# ELEC327_V4.net
KiCad netlist of a schematic drawn in EAGLE
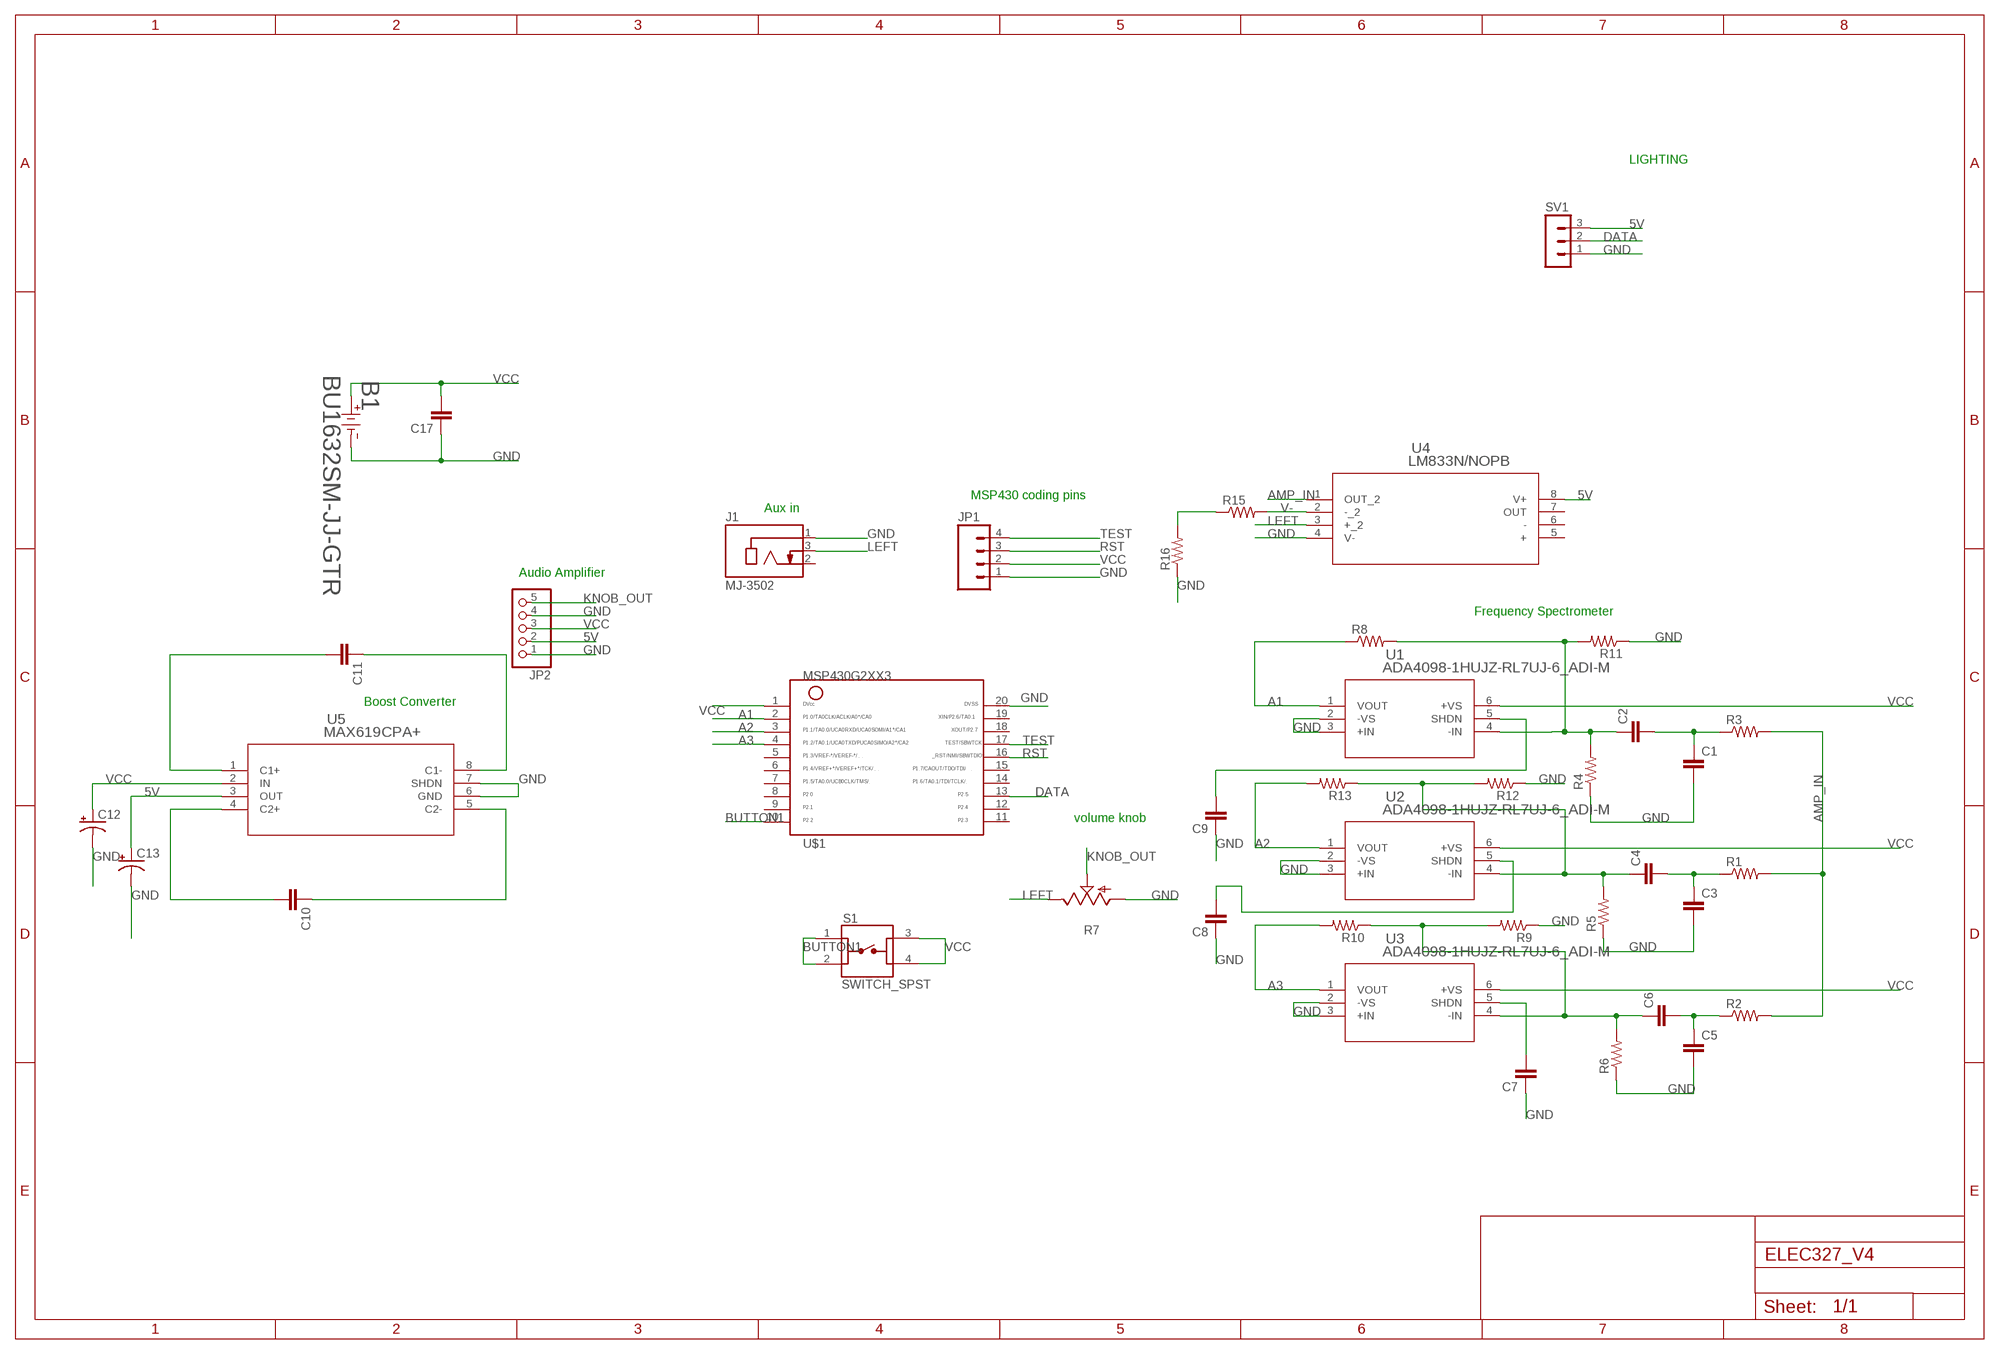
[diagram p0: schematic, sheet 1]

(export (version "E")
  (design (tool "Eeschema 10.0.6"))
  (components
    (comp (ref "B1")
      (value "BU1632SM-JJ-GTR")
      (footprint "eagle-import:BU1632SM-JJ-GTR_MPD")
      (fields (field (name "COPYRIGHT") "Copyright (C) 2023 Ultra Librarian. All rights reserved."))
      (libsource (lib "eagle-import") (part "BU1632SM-JJ-GTR"))
    )
    (comp (ref "C1")
      (value "C-EUC1206")
      (footprint "eagle-import:C1206")
      (libsource (lib "eagle-import") (part "C-EUC1206"))
    )
    (comp (ref "C2")
      (value "C-EUC1206")
      (footprint "eagle-import:C1206")
      (libsource (lib "eagle-import") (part "C-EUC1206"))
    )
    (comp (ref "C3")
      (value "C-EUC1206")
      (footprint "eagle-import:C1206")
      (libsource (lib "eagle-import") (part "C-EUC1206"))
    )
    (comp (ref "C4")
      (value "C-EUC1206")
      (footprint "eagle-import:C1206")
      (libsource (lib "eagle-import") (part "C-EUC1206"))
    )
    (comp (ref "C5")
      (value "C-EUC1206")
      (footprint "eagle-import:C1206")
      (libsource (lib "eagle-import") (part "C-EUC1206"))
    )
    (comp (ref "C6")
      (value "C-EUC1206")
      (footprint "eagle-import:C1206")
      (libsource (lib "eagle-import") (part "C-EUC1206"))
    )
    (comp (ref "C7")
      (value "C-EUC1206")
      (footprint "eagle-import:C1206")
      (libsource (lib "eagle-import") (part "C-EUC1206"))
    )
    (comp (ref "C8")
      (value "C-EUC1206")
      (footprint "eagle-import:C1206")
      (libsource (lib "eagle-import") (part "C-EUC1206"))
    )
    (comp (ref "C9")
      (value "C-EUC1206")
      (footprint "eagle-import:C1206")
      (libsource (lib "eagle-import") (part "C-EUC1206"))
    )
    (comp (ref "C10")
      (value "C-EUC1206")
      (footprint "eagle-import:C1206")
      (libsource (lib "eagle-import") (part "C-EUC1206"))
    )
    (comp (ref "C11")
      (value "C-EUC1206")
      (footprint "eagle-import:C1206")
      (libsource (lib "eagle-import") (part "C-EUC1206"))
    )
    (comp (ref "C12")
      (value "CPOL-USE5-6")
      (footprint "eagle-import:E5-6")
      (libsource (lib "eagle-import") (part "CPOL-USE5-6"))
    )
    (comp (ref "C13")
      (value "CPOL-USE5-6")
      (footprint "eagle-import:E5-6")
      (libsource (lib "eagle-import") (part "CPOL-USE5-6"))
    )
    (comp (ref "C17")
      (value "C-EUC1206")
      (footprint "eagle-import:C1206")
      (libsource (lib "eagle-import") (part "C-EUC1206"))
    )
    (comp (ref "J1")
      (value "MJ-3502")
      (footprint "eagle-import:CUI_MJ-3502")
      (fields (field (name "MANUFACTURER") "CUI INC"))
      (libsource (lib "eagle-import") (part "MJ-3502"))
    )
    (comp (ref "JP1")
      (value "HEADER_1X04LOCK")
      (footprint "eagle-import:1X04_LOCK")
      (libsource (lib "eagle-import") (part "HEADER_1X04LOCK"))
    )
    (comp (ref "JP2")
      (value "PINHD-1X55X2MM")
      (footprint "eagle-import:1_05X2MM")
      (libsource (lib "eagle-import") (part "PINHD-1X55X2MM"))
    )
    (comp (ref "R1")
      (value "R-US_R1206")
      (footprint "eagle-import:R1206")
      (libsource (lib "eagle-import") (part "R-US_R1206"))
    )
    (comp (ref "R2")
      (value "R-US_R1206")
      (footprint "eagle-import:R1206")
      (libsource (lib "eagle-import") (part "R-US_R1206"))
    )
    (comp (ref "R3")
      (value "R-US_R1206")
      (footprint "eagle-import:R1206")
      (libsource (lib "eagle-import") (part "R-US_R1206"))
    )
    (comp (ref "R4")
      (value "R-US_R1206")
      (footprint "eagle-import:R1206")
      (libsource (lib "eagle-import") (part "R-US_R1206"))
    )
    (comp (ref "R5")
      (value "R-US_R1206")
      (footprint "eagle-import:R1206")
      (libsource (lib "eagle-import") (part "R-US_R1206"))
    )
    (comp (ref "R6")
      (value "R-US_R1206")
      (footprint "eagle-import:R1206")
      (libsource (lib "eagle-import") (part "R-US_R1206"))
    )
    (comp (ref "R7")
      (value "TRIM_US-B25X")
      (footprint "eagle-import:B25X")
      (libsource (lib "eagle-import") (part "TRIM_US-B25X"))
    )
    (comp (ref "R8")
      (value "R-US_R1206")
      (footprint "eagle-import:R1206")
      (libsource (lib "eagle-import") (part "R-US_R1206"))
    )
    (comp (ref "R9")
      (value "R-US_R1206")
      (footprint "eagle-import:R1206")
      (libsource (lib "eagle-import") (part "R-US_R1206"))
    )
    (comp (ref "R10")
      (value "R-US_R1206")
      (footprint "eagle-import:R1206")
      (libsource (lib "eagle-import") (part "R-US_R1206"))
    )
    (comp (ref "R11")
      (value "R-US_R1206")
      (footprint "eagle-import:R1206")
      (libsource (lib "eagle-import") (part "R-US_R1206"))
    )
    (comp (ref "R12")
      (value "R-US_R1206")
      (footprint "eagle-import:R1206")
      (libsource (lib "eagle-import") (part "R-US_R1206"))
    )
    (comp (ref "R13")
      (value "R-US_R1206")
      (footprint "eagle-import:R1206")
      (libsource (lib "eagle-import") (part "R-US_R1206"))
    )
    (comp (ref "R15")
      (value "R-US_R1206")
      (footprint "eagle-import:R1206")
      (libsource (lib "eagle-import") (part "R-US_R1206"))
    )
    (comp (ref "R16")
      (value "R-US_R1206")
      (footprint "eagle-import:R1206")
      (libsource (lib "eagle-import") (part "R-US_R1206"))
    )
    (comp (ref "S1")
      (value "SWITCH_SPST")
      (footprint "eagle-import:SW_1825910-7")
      (fields
        (field (name "COMMENT") "1825910-7")
        (field (name "DIGI-KEY_PART_NUMBER") "450-1804-ND")
        (field (name "MF") "TE Connectivity")
      )
      (libsource (lib "eagle-import") (part "SWITCH_SPST"))
    )
    (comp (ref "SV1")
      (value "MA03-1")
      (footprint "eagle-import:MA03-1")
      (libsource (lib "eagle-import") (part "MA03-1"))
    )
    (comp (ref "U$1")
      (value "MSP430G2XX3TSSOP")
      (footprint "eagle-import:PW20")
      (libsource (lib "eagle-import") (part "MSP430G2XX3TSSOP"))
    )
    (comp (ref "U1")
      (value "ADA4098-1HUJZ-RL7UJ-6_ADI-M")
      (footprint "eagle-import:UJ-6_ADI-M")
      (fields
        (field (name "MANUFACTURER_PART_NUMBER") "ADA4098-1HUJZ-RL7")
        (field (name "COPYRIGHT") "Copyright (C) 2023 Ultra Librarian. All rights reserved.")
      )
      (libsource (lib "eagle-import") (part "ADA4098-1HUJZ-RL7UJ-6_ADI-M"))
    )
    (comp (ref "U2")
      (value "ADA4098-1HUJZ-RL7UJ-6_ADI-M")
      (footprint "eagle-import:UJ-6_ADI-M")
      (fields
        (field (name "MANUFACTURER_PART_NUMBER") "ADA4098-1HUJZ-RL7")
        (field (name "COPYRIGHT") "Copyright (C) 2023 Ultra Librarian. All rights reserved.")
      )
      (libsource (lib "eagle-import") (part "ADA4098-1HUJZ-RL7UJ-6_ADI-M"))
    )
    (comp (ref "U3")
      (value "ADA4098-1HUJZ-RL7UJ-6_ADI-M")
      (footprint "eagle-import:UJ-6_ADI-M")
      (fields
        (field (name "MANUFACTURER_PART_NUMBER") "ADA4098-1HUJZ-RL7")
        (field (name "COPYRIGHT") "Copyright (C) 2023 Ultra Librarian. All rights reserved.")
      )
      (libsource (lib "eagle-import") (part "ADA4098-1HUJZ-RL7UJ-6_ADI-M"))
    )
    (comp (ref "U4")
      (value "LM833N/NOPB")
      (footprint "eagle-import:N08E_TEX")
      (fields (field (name "COPYRIGHT") "Copyright (C) 2023 Ultra Librarian. All rights reserved."))
      (libsource (lib "eagle-import") (part "LM833N/NOPB"))
    )
    (comp (ref "U5")
      (value "MAX619CPA+")
      (footprint "eagle-import:21-0043D_8_MXM")
      (fields (field (name "COPYRIGHT") "Copyright (C) 2023 Ultra Librarian. All rights reserved."))
      (libsource (lib "eagle-import") (part "MAX619CPA+"))
    )
  )
  (nets
    (net (code "1") (name "/5V") (class "Default")
      (node (ref "C13") (pin "+") (pinfunction "+_+") (pintype "passive"))
      (node (ref "JP2") (pin "2") (pinfunction "2_2") (pintype "passive"))
      (node (ref "SV1") (pin "3") (pinfunction "3_3") (pintype "passive"))
      (node (ref "U4") (pin "8") (pinfunction "V+_8") (pintype "passive"))
      (node (ref "U5") (pin "3") (pinfunction "OUT_3") (pintype "output"))
    )
    (net (code "2") (name "/A1") (class "Default")
      (node (ref "R8") (pin "1") (pinfunction "1_1") (pintype "passive"))
      (node (ref "U$1") (pin "2") (pinfunction "2_2") (pintype "bidirectional"))
      (node (ref "U1") (pin "1") (pinfunction "VOUT_1") (pintype "output"))
    )
    (net (code "3") (name "/A2") (class "Default")
      (node (ref "R13") (pin "2") (pinfunction "2_2") (pintype "passive"))
      (node (ref "U$1") (pin "3") (pinfunction "3_3") (pintype "bidirectional"))
      (node (ref "U2") (pin "1") (pinfunction "VOUT_1") (pintype "output"))
    )
    (net (code "4") (name "/A3") (class "Default")
      (node (ref "R10") (pin "2") (pinfunction "2_2") (pintype "passive"))
      (node (ref "U$1") (pin "4") (pinfunction "4_4") (pintype "bidirectional"))
      (node (ref "U3") (pin "1") (pinfunction "VOUT_1") (pintype "output"))
    )
    (net (code "5") (name "/AMP_IN") (class "Default")
      (node (ref "R1") (pin "2") (pinfunction "2_2") (pintype "passive"))
      (node (ref "R2") (pin "2") (pinfunction "2_2") (pintype "passive"))
      (node (ref "R3") (pin "2") (pinfunction "2_2") (pintype "passive"))
      (node (ref "U4") (pin "1") (pinfunction "OUT_2_1") (pintype "passive"))
    )
    (net (code "6") (name "/BUTTON1") (class "Default")
      (node (ref "S1") (pin "1") (pinfunction "1_1") (pintype "passive"))
      (node (ref "S1") (pin "2") (pinfunction "2_2") (pintype "passive"))
      (node (ref "U$1") (pin "10") (pinfunction "10_10") (pintype "bidirectional"))
    )
    (net (code "7") (name "/DATA") (class "Default")
      (node (ref "SV1") (pin "2") (pinfunction "2_2") (pintype "passive"))
      (node (ref "U$1") (pin "13") (pinfunction "13_13") (pintype "bidirectional"))
    )
    (net (code "8") (name "/GND") (class "Default")
      (node (ref "B1") (pin "2") (pinfunction "2_2") (pintype "passive"))
      (node (ref "C1") (pin "2") (pinfunction "2_2") (pintype "passive"))
      (node (ref "C12") (pin "-") (pinfunction "-_-") (pintype "passive"))
      (node (ref "C13") (pin "-") (pinfunction "-_-") (pintype "passive"))
      (node (ref "C17") (pin "1") (pinfunction "1_1") (pintype "passive"))
      (node (ref "C3") (pin "2") (pinfunction "2_2") (pintype "passive"))
      (node (ref "C5") (pin "2") (pinfunction "2_2") (pintype "passive"))
      (node (ref "C7") (pin "1") (pinfunction "1_1") (pintype "passive"))
      (node (ref "C8") (pin "1") (pinfunction "1_1") (pintype "passive"))
      (node (ref "C9") (pin "1") (pinfunction "1_1") (pintype "passive"))
      (node (ref "J1") (pin "1") (pinfunction "1_1") (pintype "passive"))
      (node (ref "JP1") (pin "1") (pinfunction "1_1") (pintype "passive"))
      (node (ref "JP2") (pin "1") (pinfunction "1_1") (pintype "passive"))
      (node (ref "JP2") (pin "4") (pinfunction "4_4") (pintype "passive"))
      (node (ref "R11") (pin "1") (pinfunction "1_1") (pintype "passive"))
      (node (ref "R12") (pin "1") (pinfunction "1_1") (pintype "passive"))
      (node (ref "R16") (pin "1") (pinfunction "1_1") (pintype "passive"))
      (node (ref "R4") (pin "1") (pinfunction "1_1") (pintype "passive"))
      (node (ref "R5") (pin "1") (pinfunction "1_1") (pintype "passive"))
      (node (ref "R6") (pin "1") (pinfunction "1_1") (pintype "passive"))
      (node (ref "R7") (pin "A") (pinfunction "A_A") (pintype "passive"))
      (node (ref "R9") (pin "1") (pinfunction "1_1") (pintype "passive"))
      (node (ref "SV1") (pin "1") (pinfunction "1_1") (pintype "passive"))
      (node (ref "U$1") (pin "20") (pinfunction "20_20") (pintype "bidirectional"))
      (node (ref "U1") (pin "2") (pinfunction "-VS_2") (pintype "power_in"))
      (node (ref "U1") (pin "3") (pinfunction "+IN_3") (pintype "input"))
      (node (ref "U2") (pin "2") (pinfunction "-VS_2") (pintype "power_in"))
      (node (ref "U2") (pin "3") (pinfunction "+IN_3") (pintype "input"))
      (node (ref "U3") (pin "2") (pinfunction "-VS_2") (pintype "power_in"))
      (node (ref "U3") (pin "3") (pinfunction "+IN_3") (pintype "input"))
      (node (ref "U4") (pin "4") (pinfunction "V-_4") (pintype "passive"))
      (node (ref "U5") (pin "6") (pinfunction "GND_6") (pintype "passive"))
      (node (ref "U5") (pin "7") (pinfunction "SHDN_7") (pintype "input"))
    )
    (net (code "9") (name "/KNOB_OUT") (class "Default")
      (node (ref "JP2") (pin "5") (pinfunction "5_5") (pintype "passive"))
      (node (ref "R7") (pin "S") (pinfunction "S_S") (pintype "passive"))
    )
    (net (code "10") (name "/LEFT") (class "Default")
      (node (ref "J1") (pin "3") (pinfunction "3_3") (pintype "passive"))
      (node (ref "R7") (pin "E") (pinfunction "E_E") (pintype "passive"))
      (node (ref "U4") (pin "3") (pinfunction "+_2_3") (pintype "passive"))
    )
    (net (code "11") (name "/RST") (class "Default")
      (node (ref "JP1") (pin "3") (pinfunction "3_3") (pintype "passive"))
      (node (ref "U$1") (pin "16") (pinfunction "16_16") (pintype "bidirectional"))
    )
    (net (code "12") (name "/TEST") (class "Default")
      (node (ref "JP1") (pin "4") (pinfunction "4_4") (pintype "passive"))
      (node (ref "U$1") (pin "17") (pinfunction "17_17") (pintype "bidirectional"))
    )
    (net (code "13") (name "/V-") (class "Default")
      (node (ref "R15") (pin "2") (pinfunction "2_2") (pintype "passive"))
      (node (ref "U4") (pin "2") (pinfunction "-_2_2") (pintype "passive"))
    )
    (net (code "14") (name "/VCC") (class "Default")
      (node (ref "B1") (pin "1") (pinfunction "1_1") (pintype "passive"))
      (node (ref "C12") (pin "+") (pinfunction "+_+") (pintype "passive"))
      (node (ref "C17") (pin "2") (pinfunction "2_2") (pintype "passive"))
      (node (ref "JP1") (pin "2") (pinfunction "2_2") (pintype "passive"))
      (node (ref "JP2") (pin "3") (pinfunction "3_3") (pintype "passive"))
      (node (ref "S1") (pin "3") (pinfunction "3_3") (pintype "passive"))
      (node (ref "S1") (pin "4") (pinfunction "4_4") (pintype "passive"))
      (node (ref "U$1") (pin "1") (pinfunction "1_1") (pintype "bidirectional"))
      (node (ref "U1") (pin "6") (pinfunction "+VS_6") (pintype "power_in"))
      (node (ref "U2") (pin "6") (pinfunction "+VS_6") (pintype "power_in"))
      (node (ref "U3") (pin "6") (pinfunction "+VS_6") (pintype "power_in"))
      (node (ref "U5") (pin "2") (pinfunction "IN_2") (pintype "input"))
    )
    (net (code "15") (name "Net-(C1-Pad1)") (class "Default")
      (node (ref "C1") (pin "1") (pinfunction "1_1") (pintype "passive"))
      (node (ref "C2") (pin "2") (pinfunction "2_2") (pintype "passive"))
      (node (ref "R3") (pin "1") (pinfunction "1_1") (pintype "passive"))
    )
    (net (code "16") (name "Net-(C3-Pad1)") (class "Default")
      (node (ref "C3") (pin "1") (pinfunction "1_1") (pintype "passive"))
      (node (ref "C4") (pin "2") (pinfunction "2_2") (pintype "passive"))
      (node (ref "R1") (pin "1") (pinfunction "1_1") (pintype "passive"))
    )
    (net (code "17") (name "Net-(C5-Pad1)") (class "Default")
      (node (ref "C5") (pin "1") (pinfunction "1_1") (pintype "passive"))
      (node (ref "C6") (pin "2") (pinfunction "2_2") (pintype "passive"))
      (node (ref "R2") (pin "1") (pinfunction "1_1") (pintype "passive"))
    )
    (net (code "18") (name "Net-(R15-Pad1)") (class "Default")
      (node (ref "R15") (pin "1") (pinfunction "1_1") (pintype "passive"))
      (node (ref "R16") (pin "2") (pinfunction "2_2") (pintype "passive"))
    )
    (net (code "19") (name "Net-(U1--IN)") (class "Default")
      (node (ref "C2") (pin "1") (pinfunction "1_1") (pintype "passive"))
      (node (ref "R11") (pin "2") (pinfunction "2_2") (pintype "passive"))
      (node (ref "R4") (pin "2") (pinfunction "2_2") (pintype "passive"))
      (node (ref "R8") (pin "2") (pinfunction "2_2") (pintype "passive"))
      (node (ref "U1") (pin "4") (pinfunction "-IN_4") (pintype "input"))
    )
    (net (code "20") (name "Net-(U1-SHDN)") (class "Default")
      (node (ref "C9") (pin "2") (pinfunction "2_2") (pintype "passive"))
      (node (ref "U1") (pin "5") (pinfunction "SHDN_5") (pintype "input"))
    )
    (net (code "21") (name "Net-(U2--IN)") (class "Default")
      (node (ref "C4") (pin "1") (pinfunction "1_1") (pintype "passive"))
      (node (ref "R12") (pin "2") (pinfunction "2_2") (pintype "passive"))
      (node (ref "R13") (pin "1") (pinfunction "1_1") (pintype "passive"))
      (node (ref "R5") (pin "2") (pinfunction "2_2") (pintype "passive"))
      (node (ref "U2") (pin "4") (pinfunction "-IN_4") (pintype "input"))
    )
    (net (code "22") (name "Net-(U2-SHDN)") (class "Default")
      (node (ref "C8") (pin "2") (pinfunction "2_2") (pintype "passive"))
      (node (ref "U2") (pin "5") (pinfunction "SHDN_5") (pintype "input"))
    )
    (net (code "23") (name "Net-(U3--IN)") (class "Default")
      (node (ref "C6") (pin "1") (pinfunction "1_1") (pintype "passive"))
      (node (ref "R10") (pin "1") (pinfunction "1_1") (pintype "passive"))
      (node (ref "R6") (pin "2") (pinfunction "2_2") (pintype "passive"))
      (node (ref "R9") (pin "2") (pinfunction "2_2") (pintype "passive"))
      (node (ref "U3") (pin "4") (pinfunction "-IN_4") (pintype "input"))
    )
    (net (code "24") (name "Net-(U3-SHDN)") (class "Default")
      (node (ref "C7") (pin "2") (pinfunction "2_2") (pintype "passive"))
      (node (ref "U3") (pin "5") (pinfunction "SHDN_5") (pintype "input"))
    )
    (net (code "25") (name "Net-(U5-C1+)") (class "Default")
      (node (ref "C11") (pin "2") (pinfunction "2_2") (pintype "passive"))
      (node (ref "U5") (pin "1") (pinfunction "C1+_1") (pintype "passive"))
    )
    (net (code "26") (name "Net-(U5-C1-)") (class "Default")
      (node (ref "C11") (pin "1") (pinfunction "1_1") (pintype "passive"))
      (node (ref "U5") (pin "8") (pinfunction "C1-_8") (pintype "passive"))
    )
    (net (code "27") (name "Net-(U5-C2+)") (class "Default")
      (node (ref "C10") (pin "2") (pinfunction "2_2") (pintype "passive"))
      (node (ref "U5") (pin "4") (pinfunction "C2+_4") (pintype "passive"))
    )
    (net (code "28") (name "Net-(U5-C2-)") (class "Default")
      (node (ref "C10") (pin "1") (pinfunction "1_1") (pintype "passive"))
      (node (ref "U5") (pin "5") (pinfunction "C2-_5") (pintype "passive"))
    )
    (net (code "29") (name "unconnected-(J1-Pad2)") (class "Default")
      (node (ref "J1") (pin "2") (pinfunction "2_2") (pintype "passive"))
    )
    (net (code "30") (name "unconnected-(U$1-Pad5)") (class "Default")
      (node (ref "U$1") (pin "5") (pinfunction "5_5") (pintype "bidirectional"))
    )
    (net (code "31") (name "unconnected-(U$1-Pad6)") (class "Default")
      (node (ref "U$1") (pin "6") (pinfunction "6_6") (pintype "bidirectional"))
    )
    (net (code "32") (name "unconnected-(U$1-Pad7)") (class "Default")
      (node (ref "U$1") (pin "7") (pinfunction "7_7") (pintype "bidirectional"))
    )
    (net (code "33") (name "unconnected-(U$1-Pad8)") (class "Default")
      (node (ref "U$1") (pin "8") (pinfunction "8_8") (pintype "bidirectional"))
    )
    (net (code "34") (name "unconnected-(U$1-Pad9)") (class "Default")
      (node (ref "U$1") (pin "9") (pinfunction "9_9") (pintype "bidirectional"))
    )
    (net (code "35") (name "unconnected-(U$1-Pad11)") (class "Default")
      (node (ref "U$1") (pin "11") (pinfunction "11_11") (pintype "bidirectional"))
    )
    (net (code "36") (name "unconnected-(U$1-Pad12)") (class "Default")
      (node (ref "U$1") (pin "12") (pinfunction "12_12") (pintype "bidirectional"))
    )
    (net (code "37") (name "unconnected-(U$1-Pad14)") (class "Default")
      (node (ref "U$1") (pin "14") (pinfunction "14_14") (pintype "bidirectional"))
    )
    (net (code "38") (name "unconnected-(U$1-Pad15)") (class "Default")
      (node (ref "U$1") (pin "15") (pinfunction "15_15") (pintype "bidirectional"))
    )
    (net (code "39") (name "unconnected-(U$1-Pad18)") (class "Default")
      (node (ref "U$1") (pin "18") (pinfunction "18_18") (pintype "bidirectional"))
    )
    (net (code "40") (name "unconnected-(U$1-Pad19)") (class "Default")
      (node (ref "U$1") (pin "19") (pinfunction "19_19") (pintype "bidirectional"))
    )
    (net (code "41") (name "unconnected-(U4-+-Pad5)") (class "Default")
      (node (ref "U4") (pin "5") (pinfunction "+_5") (pintype "passive"))
    )
    (net (code "42") (name "unconnected-(U4---Pad6)") (class "Default")
      (node (ref "U4") (pin "6") (pinfunction "-_6") (pintype "passive"))
    )
    (net (code "43") (name "unconnected-(U4-OUT-Pad7)") (class "Default")
      (node (ref "U4") (pin "7") (pinfunction "OUT_7") (pintype "passive"))
    )
  )
)
